# mainBoard.net
KiCad netlist of a schematic drawn in EAGLE
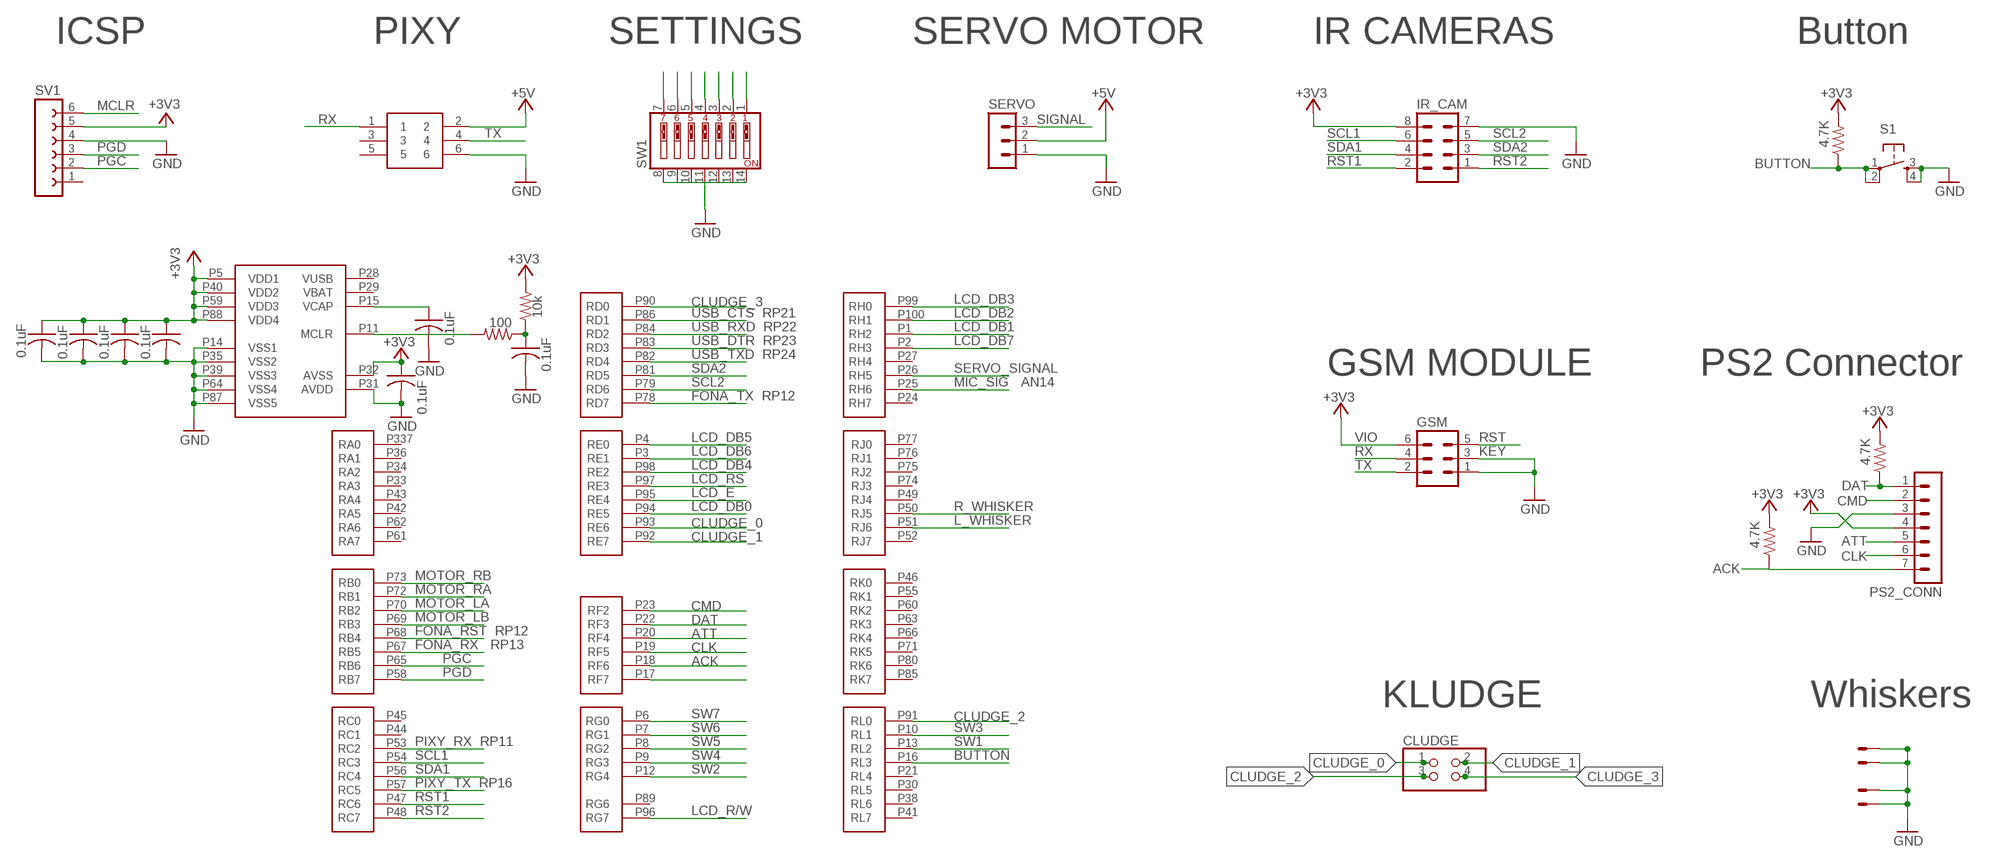
[diagram p0: schematic, sheet 1]
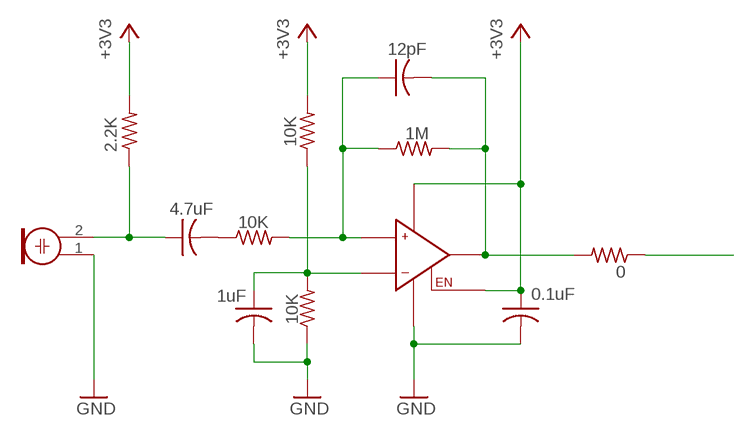
[diagram p1: schematic, sheet 2]
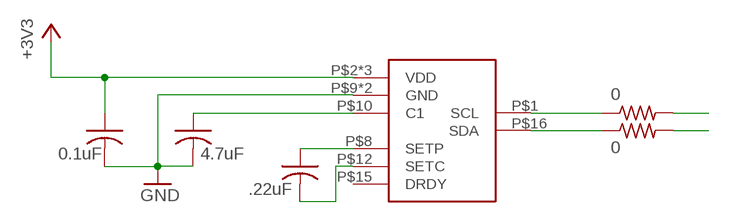
[diagram p2: schematic, sheet 3]
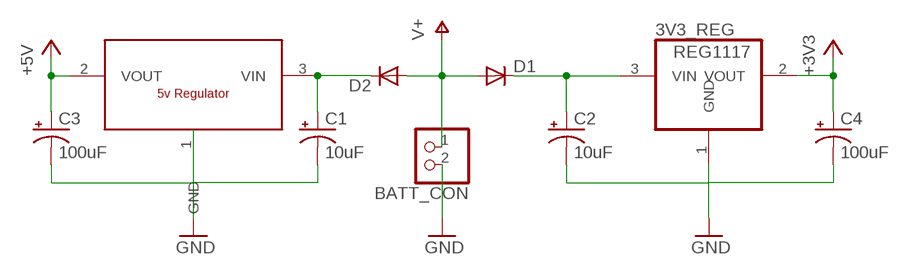
[diagram p3: schematic, sheet 4]
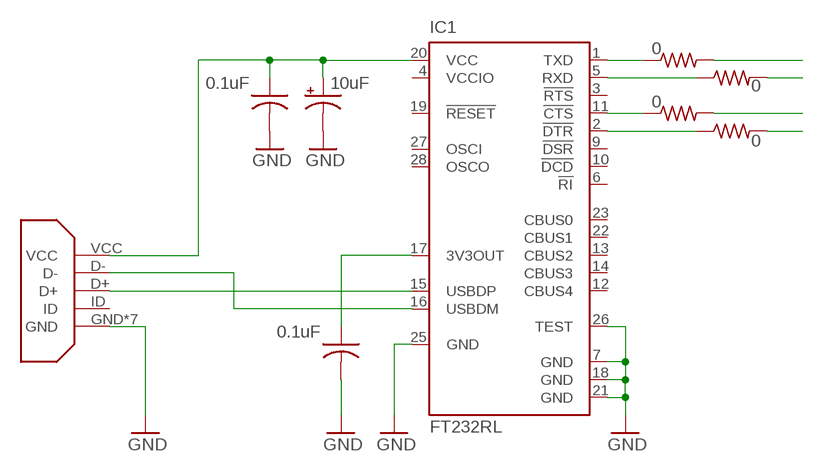
[diagram p4: schematic, sheet 5]
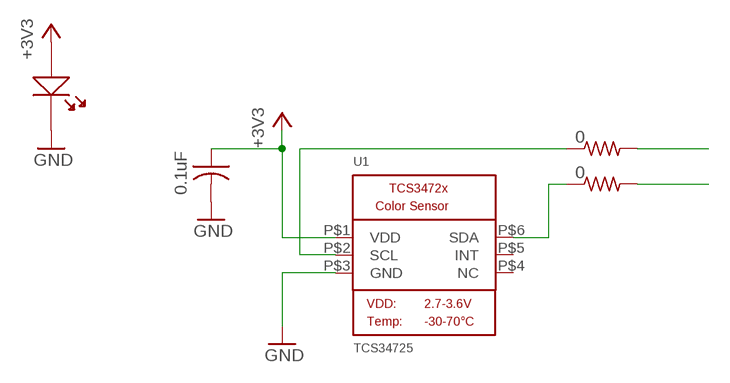
[diagram p5: schematic, sheet 6]
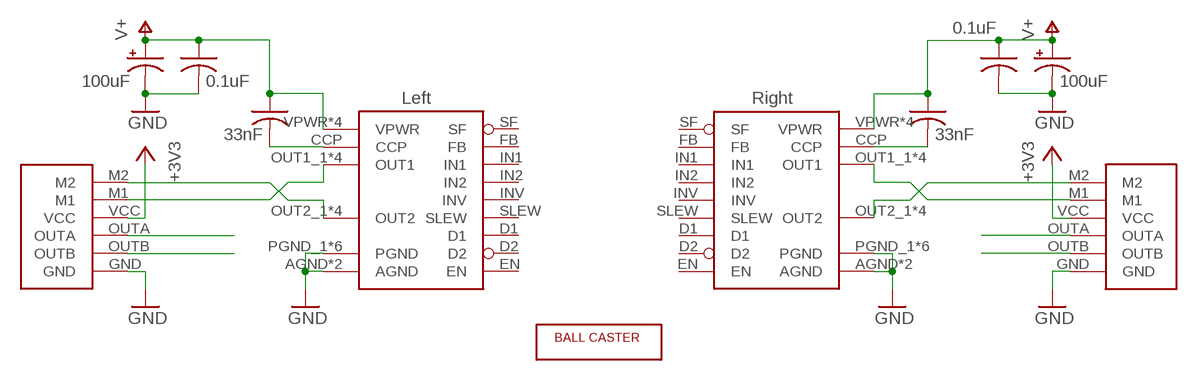
[diagram p6: schematic, sheet 7]
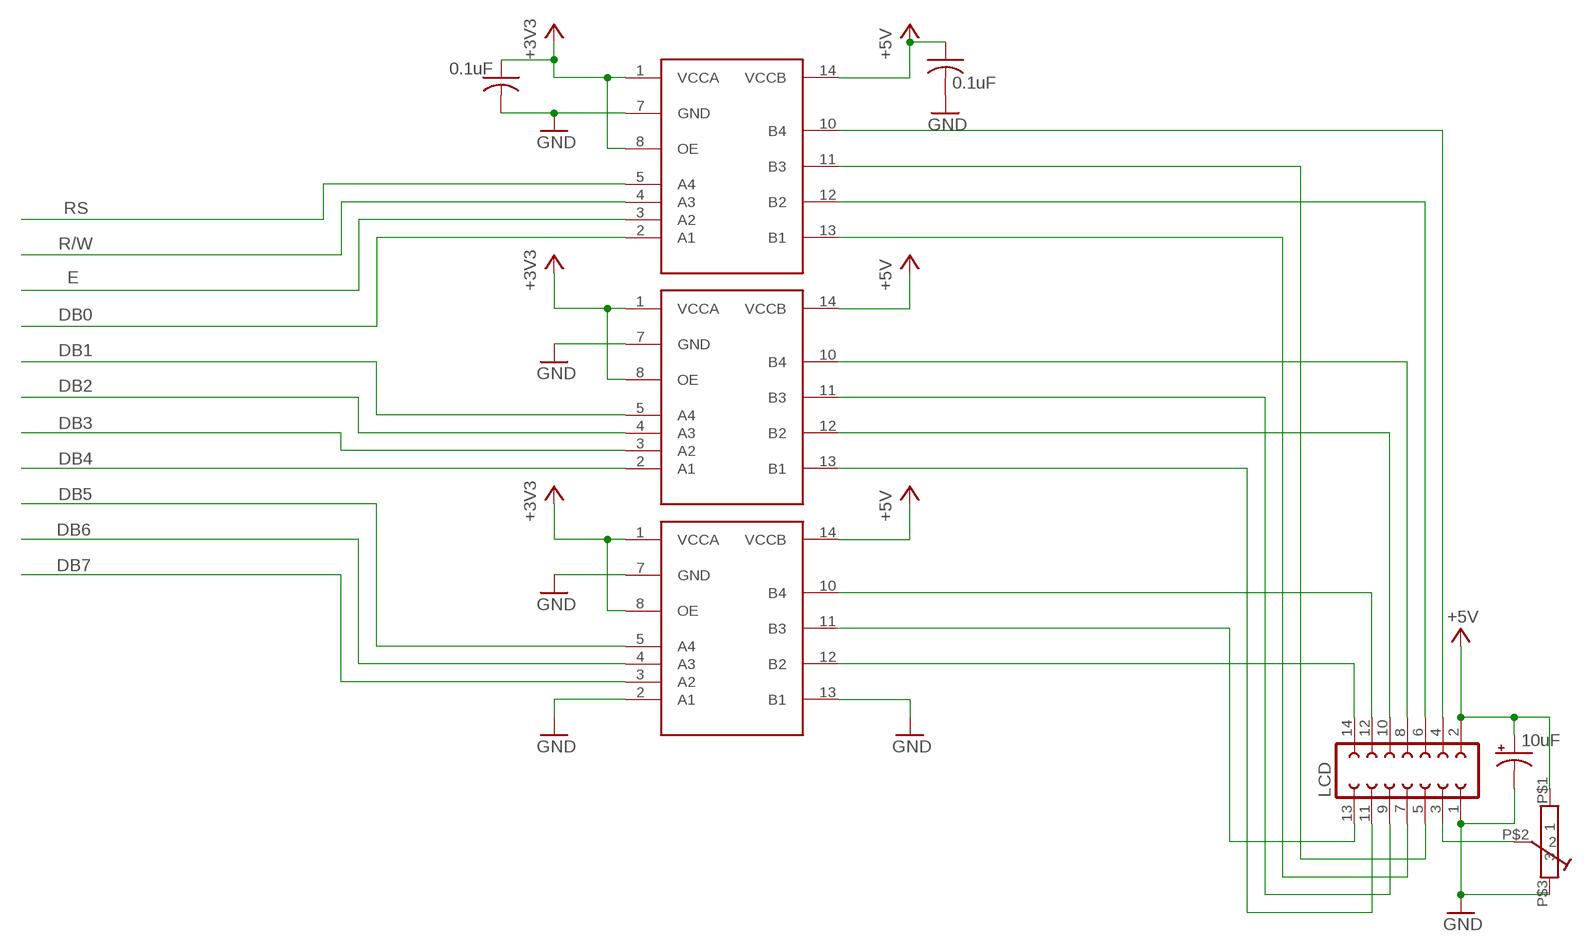
[diagram p7: schematic, sheet 8]

(export (version "E")
  (design (tool "Eeschema 10.0.6"))
  (components
    (comp (ref "C15")
      (value "0.1uF")
      (footprint "eagle-import:C0805")
      (libsource (lib "eagle-import") (part "C-USC0805"))
    )
    (comp (ref "R14")
      (value "0")
      (footprint "eagle-import:R0805")
      (libsource (lib "eagle-import") (part "R-US_R0805"))
    )
    (comp (ref "R15")
      (value "0")
      (footprint "eagle-import:R0805")
      (libsource (lib "eagle-import") (part "R-US_R0805"))
    )
    (comp (ref "U$5")
      (value "LED")
      (footprint "eagle-import:LED")
      (libsource (lib "eagle-import") (part "LED"))
    )
    (comp (ref "U1")
      (value "TCS34725")
      (footprint "eagle-import:TCS3472_FN6")
      (libsource (lib "eagle-import") (part "LIGHT_TCS3472"))
    )
    (comp (ref "C22")
      (value "33nF")
      (footprint "eagle-import:C0805")
      (libsource (lib "eagle-import") (part "C-USC0805"))
    )
    (comp (ref "C23")
      (value "0.1uF")
      (footprint "eagle-import:C0805")
      (libsource (lib "eagle-import") (part "C-USC0805"))
    )
    (comp (ref "C24")
      (value "100uF")
      (footprint "eagle-import:UD-4X5,8_NICHICON")
      (libsource (lib "eagle-import") (part "CPOL-USUD-4X5,8"))
    )
    (comp (ref "C25")
      (value "33nF")
      (footprint "eagle-import:C0805")
      (libsource (lib "eagle-import") (part "C-USC0805"))
    )
    (comp (ref "C26")
      (value "0.1uF")
      (footprint "eagle-import:C0805")
      (libsource (lib "eagle-import") (part "C-USC0805"))
    )
    (comp (ref "C27")
      (value "100uF")
      (footprint "eagle-import:UD-4X5,8_NICHICON")
      (libsource (lib "eagle-import") (part "CPOL-USUD-4X5,8"))
    )
    (comp (ref "U$7")
      (value "POLOLU_BALLCASTER")
      (footprint "eagle-import:CASTER")
      (libsource (lib "eagle-import") (part "POLOLU_BALLCASTER"))
    )
    (comp (ref "U$8")
      (value "POLOLU_MOTORDRIVE")
      (footprint "eagle-import:MOTOR")
      (libsource (lib "eagle-import") (part "POLOLU_MOTORDRIVE"))
    )
    (comp (ref "U$9")
      (value "POLOLU_MOTORDRIVE")
      (footprint "eagle-import:MOTOR")
      (libsource (lib "eagle-import") (part "POLOLU_MOTORDRIVE"))
    )
    (comp (ref "U$10")
      (value "MOTORDRIVE")
      (footprint "eagle-import:PQFN")
      (libsource (lib "eagle-import") (part "MOTORDRIVE"))
    )
    (comp (ref "U$11")
      (value "MOTORDRIVE")
      (footprint "eagle-import:PQFN")
      (libsource (lib "eagle-import") (part "MOTORDRIVE"))
    )
    (comp (ref "C16")
      (value "0.1uF")
      (footprint "eagle-import:C0805")
      (libsource (lib "eagle-import") (part "C-USC0805"))
    )
    (comp (ref "C18")
      (value "0.1uF")
      (footprint "eagle-import:C0805")
      (libsource (lib "eagle-import") (part "C-USC0805"))
    )
    (comp (ref "C19")
      (value "0.1uF")
      (footprint "eagle-import:C0805")
      (libsource (lib "eagle-import") (part "C-USC0805"))
    )
    (comp (ref "C20")
      (value "0.1uF")
      (footprint "eagle-import:C0805")
      (libsource (lib "eagle-import") (part "C-USC0805"))
    )
    (comp (ref "C28")
      (value "0.1uF")
      (footprint "eagle-import:C0805")
      (libsource (lib "eagle-import") (part "C-USC0805"))
    )
    (comp (ref "C29")
      (value "0.1uF")
      (footprint "eagle-import:C0805")
      (libsource (lib "eagle-import") (part "C-USC0805"))
    )
    (comp (ref "C30")
      (value "0.1uF")
      (footprint "eagle-import:C0805")
      (libsource (lib "eagle-import") (part "C-USC0805"))
    )
    (comp (ref "CLUDGE")
      (value "PINHD-2X2")
      (footprint "eagle-import:2X02")
      (libsource (lib "eagle-import") (part "PINHD-2X2"))
    )
    (comp (ref "GSM")
      (value "MA03-2")
      (footprint "eagle-import:MA03-2")
      (libsource (lib "eagle-import") (part "MA03-2"))
    )
    (comp (ref "IR_CAM")
      (value "MA04-2")
      (footprint "eagle-import:MA04-2")
      (libsource (lib "eagle-import") (part "MA04-2"))
    )
    (comp (ref "PS2_CONN")
      (value "MA07-1")
      (footprint "eagle-import:MA07-1")
      (libsource (lib "eagle-import") (part "MA07-1"))
    )
    (comp (ref "R16")
      (value "100")
      (footprint "eagle-import:R0805")
      (libsource (lib "eagle-import") (part "R-US_R0805"))
    )
    (comp (ref "R17")
      (value "10k")
      (footprint "eagle-import:R0805")
      (libsource (lib "eagle-import") (part "R-US_R0805"))
    )
    (comp (ref "R18")
      (value "4.7K")
      (footprint "eagle-import:M0805")
      (libsource (lib "eagle-import") (part "resistor_R-US_M0805"))
    )
    (comp (ref "R19")
      (value "4.7K")
      (footprint "eagle-import:M0805")
      (libsource (lib "eagle-import") (part "resistor_R-US_M0805"))
    )
    (comp (ref "R20")
      (value "4.7K")
      (footprint "eagle-import:M0805")
      (libsource (lib "eagle-import") (part "resistor_R-US_M0805"))
    )
    (comp (ref "S1")
      (value "10-XX")
      (footprint "eagle-import:B3F-10XX")
      (fields (field (name "MPN") "B3F-1000"))
      (libsource (lib "eagle-import") (part "10-XX"))
    )
    (comp (ref "SERVO")
      (value "MA03-1")
      (footprint "eagle-import:MA03-1")
      (libsource (lib "eagle-import") (part "MA03-1"))
    )
    (comp (ref "SV1")
      (value "FE06-1")
      (footprint "eagle-import:FE06")
      (libsource (lib "eagle-import") (part "FE06-1"))
    )
    (comp (ref "SW1")
      (value "SW_DIP-7")
      (footprint "eagle-import:EDG-07")
      (libsource (lib "eagle-import") (part "SW_DIP-7"))
    )
    (comp (ref "U$1")
      (value "PIC18F97J94")
      (footprint "eagle-import:QTFP-100")
      (libsource (lib "eagle-import") (part "PIC18F97J94"))
    )
    (comp (ref "U$15")
      (value "PIXY")
      (footprint "eagle-import:PIXY_HEADER")
      (libsource (lib "eagle-import") (part "PIXY"))
    )
    (comp (ref "X1")
      (value "22-23-2021")
      (footprint "eagle-import:22-23-2021")
      (fields (field (name "MF") "MOLEX"))
      (libsource (lib "eagle-import") (part "22-23-2021"))
    )
    (comp (ref "X2")
      (value "22-23-2021")
      (footprint "eagle-import:22-23-2021")
      (fields (field (name "MF") "MOLEX"))
      (libsource (lib "eagle-import") (part "22-23-2021"))
    )
    (comp (ref "10UF")
      (value "10uF")
      (footprint "eagle-import:UD-4X5,8_NICHICON")
      (libsource (lib "eagle-import") (part "CPOL-USUD-4X5,8"))
    )
    (comp (ref "C17")
      (value "0.1uF")
      (footprint "eagle-import:C0805")
      (libsource (lib "eagle-import") (part "C-USC0805"))
    )
    (comp (ref "C21")
      (value "0.1uF")
      (footprint "eagle-import:C0805")
      (libsource (lib "eagle-import") (part "C-USC0805"))
    )
    (comp (ref "LCD")
      (value "FE07-2")
      (footprint "eagle-import:FE07-2")
      (libsource (lib "eagle-import") (part "FE07-2"))
    )
    (comp (ref "U$6")
      (value "PVG3G-SMD-TRIMMER")
      (footprint "eagle-import:PVG3G-SMT-TRIMMER")
      (libsource (lib "eagle-import") (part "PVG3G-SMD-TRIMMER"))
    )
    (comp (ref "U$12")
      (value "TXB0104")
      (footprint "eagle-import:S-PVQFN-N14")
      (libsource (lib "eagle-import") (part "TXB0104"))
    )
    (comp (ref "U$13")
      (value "TXB0104")
      (footprint "eagle-import:S-PVQFN-N14")
      (libsource (lib "eagle-import") (part "TXB0104"))
    )
    (comp (ref "U$14")
      (value "TXB0104")
      (footprint "eagle-import:S-PVQFN-N14")
      (libsource (lib "eagle-import") (part "TXB0104"))
    )
    (comp (ref "C11")
      (value "1uF")
      (footprint "eagle-import:C0805")
      (libsource (lib "eagle-import") (part "C-USC0805"))
    )
    (comp (ref "C12")
      (value "4.7uF")
      (footprint "eagle-import:C0805")
      (libsource (lib "eagle-import") (part "C-USC0805"))
    )
    (comp (ref "C13")
      (value "12pF")
      (footprint "eagle-import:C0805")
      (libsource (lib "eagle-import") (part "C-USC0805"))
    )
    (comp (ref "C14")
      (value "0.1uF")
      (footprint "eagle-import:C0805")
      (libsource (lib "eagle-import") (part "C-USC0805"))
    )
    (comp (ref "M1")
      (value "ELECTRET_MICROPHON-WM-63PR")
      (footprint "eagle-import:WM-63PR")
      (libsource (lib "eagle-import") (part "ELECTRET_MICROPHON-WM-63PR"))
    )
    (comp (ref "R1")
      (value "10K")
      (footprint "eagle-import:R0805")
      (libsource (lib "eagle-import") (part "R-US_R0805"))
    )
    (comp (ref "R2")
      (value "1M")
      (footprint "eagle-import:R0805")
      (libsource (lib "eagle-import") (part "R-US_R0805"))
    )
    (comp (ref "R4")
      (value "2.2K")
      (footprint "eagle-import:R0805")
      (libsource (lib "eagle-import") (part "R-US_R0805"))
    )
    (comp (ref "R5")
      (value "10K")
      (footprint "eagle-import:R0805")
      (libsource (lib "eagle-import") (part "R-US_R0805"))
    )
    (comp (ref "R6")
      (value "10K")
      (footprint "eagle-import:R0805")
      (libsource (lib "eagle-import") (part "R-US_R0805"))
    )
    (comp (ref "R7")
      (value "0")
      (footprint "eagle-import:R0805")
      (libsource (lib "eagle-import") (part "R-US_R0805"))
    )
    (comp (ref "U$4")
      (value "OPA334")
      (footprint "eagle-import:OPA334")
      (libsource (lib "eagle-import") (part "OPA334"))
    )
    (comp (ref "3V3_REG")
      (value "REG1117")
      (footprint "eagle-import:SOT223")
      (libsource (lib "eagle-import") (part "REG1117"))
    )
    (comp (ref "5V_REG")
      (value "NCP1117-DPAK")
      (footprint "eagle-import:DPAK-2")
      (libsource (lib "eagle-import") (part "NCP1117-DPAK"))
    )
    (comp (ref "BATT_CON")
      (value "JST_2PIN-THM")
      (footprint "eagle-import:JST-PH-2-THM")
      (libsource (lib "eagle-import") (part "JST_2PIN-THM"))
    )
    (comp (ref "C1")
      (value "10uF")
      (footprint "eagle-import:UD-4X5,8_NICHICON")
      (libsource (lib "eagle-import") (part "CPOL-USUD-4X5,8"))
    )
    (comp (ref "C2")
      (value "10uF")
      (footprint "eagle-import:UD-4X5,8_NICHICON")
      (libsource (lib "eagle-import") (part "CPOL-USUD-4X5,8"))
    )
    (comp (ref "C3")
      (value "100uF")
      (footprint "eagle-import:UD-6,3X5,8_NICHICON")
      (libsource (lib "eagle-import") (part "CPOL-USUD-6,3X5,8"))
    )
    (comp (ref "C4")
      (value "100uF")
      (footprint "eagle-import:UD-6,3X5,8_NICHICON")
      (libsource (lib "eagle-import") (part "CPOL-USUD-6,3X5,8"))
    )
    (comp (ref "D1")
      (value "DIODE-SOD123")
      (footprint "eagle-import:SOD123")
      (libsource (lib "eagle-import") (part "DIODE-SOD123"))
    )
    (comp (ref "D2")
      (value "DIODE-SOD123")
      (footprint "eagle-import:SOD123")
      (libsource (lib "eagle-import") (part "DIODE-SOD123"))
    )
    (comp (ref "C8")
      (value ".22uF")
      (footprint "eagle-import:C0805")
      (libsource (lib "eagle-import") (part "C-USC0805"))
    )
    (comp (ref "C9")
      (value "4.7uF")
      (footprint "eagle-import:C0805")
      (libsource (lib "eagle-import") (part "C-USC0805"))
    )
    (comp (ref "C10")
      (value "0.1uF")
      (footprint "eagle-import:C0805")
      (libsource (lib "eagle-import") (part "C-USC0805"))
    )
    (comp (ref "R8")
      (value "0")
      (footprint "eagle-import:R0805")
      (libsource (lib "eagle-import") (part "R-US_R0805"))
    )
    (comp (ref "R9")
      (value "0")
      (footprint "eagle-import:R0805")
      (libsource (lib "eagle-import") (part "R-US_R0805"))
    )
    (comp (ref "U$3")
      (value "HMC5883L")
      (footprint "eagle-import:HMC5883L")
      (libsource (lib "eagle-import") (part "HMC5883L"))
    )
    (comp (ref "C5")
      (value "0.1uF")
      (footprint "eagle-import:C0805")
      (libsource (lib "eagle-import") (part "C-USC0805"))
    )
    (comp (ref "C6")
      (value "10uF")
      (footprint "eagle-import:UD-4X5,8_NICHICON")
      (libsource (lib "eagle-import") (part "CPOL-USUD-4X5,8"))
    )
    (comp (ref "C7")
      (value "0.1uF")
      (footprint "eagle-import:C0805")
      (libsource (lib "eagle-import") (part "C-USC0805"))
    )
    (comp (ref "IC1")
      (value "FT232RL")
      (footprint "eagle-import:SSOP28")
      (libsource (lib "eagle-import") (part "FT232RL"))
    )
    (comp (ref "R10")
      (value "0")
      (footprint "eagle-import:R0805")
      (libsource (lib "eagle-import") (part "R-US_R0805"))
    )
    (comp (ref "R11")
      (value "0")
      (footprint "eagle-import:R0805")
      (libsource (lib "eagle-import") (part "R-US_R0805"))
    )
    (comp (ref "R12")
      (value "0")
      (footprint "eagle-import:R0805")
      (libsource (lib "eagle-import") (part "R-US_R0805"))
    )
    (comp (ref "R13")
      (value "0")
      (footprint "eagle-import:R0805")
      (libsource (lib "eagle-import") (part "R-US_R0805"))
    )
    (comp (ref "U$2")
      (value "MICRO_USB")
      (footprint "eagle-import:MICRO_USB_FCI")
      (libsource (lib "eagle-import") (part "MICRO_USB"))
    )
  )
  (nets
    (net (code "1") (name "+3V3") (class "Default")
      (node (ref "3V3_REG") (pin "2") (pinfunction "VOUT_2") (pintype "output"))
      (node (ref "C10") (pin "1") (pinfunction "1_1") (pintype "passive"))
      (node (ref "C14") (pin "1") (pinfunction "1_1") (pintype "passive"))
      (node (ref "C15") (pin "1") (pinfunction "1_1") (pintype "passive"))
      (node (ref "C16") (pin "1") (pinfunction "1_1") (pintype "passive"))
      (node (ref "C17") (pin "1") (pinfunction "1_1") (pintype "passive"))
      (node (ref "C18") (pin "1") (pinfunction "1_1") (pintype "passive"))
      (node (ref "C19") (pin "1") (pinfunction "1_1") (pintype "passive"))
      (node (ref "C20") (pin "1") (pinfunction "1_1") (pintype "passive"))
      (node (ref "C28") (pin "1") (pinfunction "1_1") (pintype "passive"))
      (node (ref "C4") (pin "+") (pinfunction "+_+") (pintype "passive"))
      (node (ref "GSM") (pin "6") (pinfunction "6_6") (pintype "passive"))
      (node (ref "IR_CAM") (pin "8") (pinfunction "8_8") (pintype "passive"))
      (node (ref "PS2_CONN") (pin "4") (pinfunction "4_4") (pintype "passive"))
      (node (ref "R17") (pin "2") (pinfunction "2_2") (pintype "passive"))
      (node (ref "R18") (pin "2") (pinfunction "2_2") (pintype "passive"))
      (node (ref "R19") (pin "2") (pinfunction "2_2") (pintype "passive"))
      (node (ref "R20") (pin "2") (pinfunction "2_2") (pintype "passive"))
      (node (ref "R4") (pin "2") (pinfunction "2_2") (pintype "passive"))
      (node (ref "R5") (pin "2") (pinfunction "2_2") (pintype "passive"))
      (node (ref "SV1") (pin "5") (pinfunction "5_5") (pintype "passive"))
      (node (ref "U$1") (pin "P32") (pinfunction "AVSS_P32") (pintype "bidirectional"))
      (node (ref "U$1") (pin "P40") (pinfunction "VDD2_P40") (pintype "bidirectional"))
      (node (ref "U$1") (pin "P5") (pinfunction "VDD1_P5") (pintype "bidirectional"))
      (node (ref "U$1") (pin "P59") (pinfunction "VDD3_P59") (pintype "bidirectional"))
      (node (ref "U$1") (pin "P88") (pinfunction "VDD4_P88") (pintype "bidirectional"))
      (node (ref "U$12") (pin "1") (pinfunction "VCCA_1") (pintype "power_in"))
      (node (ref "U$12") (pin "8") (pinfunction "OE_8") (pintype "bidirectional"))
      (node (ref "U$13") (pin "1") (pinfunction "VCCA_1") (pintype "power_in"))
      (node (ref "U$13") (pin "8") (pinfunction "OE_8") (pintype "bidirectional"))
      (node (ref "U$14") (pin "1") (pinfunction "VCCA_1") (pintype "power_in"))
      (node (ref "U$14") (pin "8") (pinfunction "OE_8") (pintype "bidirectional"))
      (node (ref "U$3") (pin "P$13") (pinfunction "VDD_P$13") (pintype "bidirectional"))
      (node (ref "U$3") (pin "P$2") (pinfunction "VDD_P$2") (pintype "bidirectional"))
      (node (ref "U$3") (pin "P$4") (pinfunction "VDD_P$4") (pintype "bidirectional"))
      (node (ref "U$4") (pin "P$5") (pinfunction "EN_P$5") (pintype "bidirectional"))
      (node (ref "U$4") (pin "P$6") (pinfunction "V+_P$6") (pintype "bidirectional"))
      (node (ref "U$5") (pin "ANODE") (pinfunction "ANODE_ANODE") (pintype "bidirectional"))
      (node (ref "U$8") (pin "VCC") (pinfunction "VCC_VCC") (pintype "bidirectional"))
      (node (ref "U$9") (pin "VCC") (pinfunction "VCC_VCC") (pintype "bidirectional"))
      (node (ref "U1") (pin "P$1") (pinfunction "VDD_P$1") (pintype "power_in"))
    )
    (net (code "2") (name "+5V") (class "Default")
      (node (ref "10UF") (pin "+") (pinfunction "+_+") (pintype "passive"))
      (node (ref "5V_REG") (pin "2") (pinfunction "VOUT_2") (pintype "bidirectional"))
      (node (ref "C21") (pin "1") (pinfunction "1_1") (pintype "passive"))
      (node (ref "C3") (pin "+") (pinfunction "+_+") (pintype "passive"))
      (node (ref "LCD") (pin "2") (pinfunction "2_2") (pintype "passive"))
      (node (ref "SERVO") (pin "2") (pinfunction "2_2") (pintype "passive"))
      (node (ref "U$12") (pin "14") (pinfunction "VCCB_14") (pintype "power_in"))
      (node (ref "U$13") (pin "14") (pinfunction "VCCB_14") (pintype "power_in"))
      (node (ref "U$14") (pin "14") (pinfunction "VCCB_14") (pintype "power_in"))
      (node (ref "U$15") (pin "2") (pinfunction "2_2") (pintype "bidirectional"))
      (node (ref "U$6") (pin "P$1") (pinfunction "1_P$1") (pintype "power_in"))
    )
    (net (code "3") (name "ACK") (class "Default")
      (node (ref "PS2_CONN") (pin "7") (pinfunction "7_7") (pintype "passive"))
      (node (ref "R20") (pin "1") (pinfunction "1_1") (pintype "passive"))
      (node (ref "U$1") (pin "P18") (pinfunction "RF6_P18") (pintype "bidirectional"))
    )
    (net (code "4") (name "ATT") (class "Default")
      (node (ref "PS2_CONN") (pin "5") (pinfunction "5_5") (pintype "passive"))
      (node (ref "U$1") (pin "P20") (pinfunction "RF4_P20") (pintype "bidirectional"))
    )
    (net (code "5") (name "BUTTON") (class "Default")
      (node (ref "R18") (pin "1") (pinfunction "1_1") (pintype "passive"))
      (node (ref "S1") (pin "1") (pinfunction "P_1") (pintype "passive"))
      (node (ref "S1") (pin "2") (pinfunction "P1_2") (pintype "passive"))
      (node (ref "U$1") (pin "P16") (pinfunction "RL3_P16") (pintype "bidirectional"))
    )
    (net (code "6") (name "CLK") (class "Default")
      (node (ref "PS2_CONN") (pin "6") (pinfunction "6_6") (pintype "passive"))
      (node (ref "U$1") (pin "P19") (pinfunction "RF5_P19") (pintype "bidirectional"))
    )
    (net (code "7") (name "CLUDGE_0") (class "Default")
      (node (ref "CLUDGE") (pin "1") (pinfunction "1_1") (pintype "passive"))
      (node (ref "U$1") (pin "P93") (pinfunction "RE6_P93") (pintype "bidirectional"))
    )
    (net (code "8") (name "CLUDGE_1") (class "Default")
      (node (ref "CLUDGE") (pin "2") (pinfunction "2_2") (pintype "passive"))
      (node (ref "U$1") (pin "P92") (pinfunction "RE7_P92") (pintype "bidirectional"))
    )
    (net (code "9") (name "CLUDGE_2") (class "Default")
      (node (ref "CLUDGE") (pin "3") (pinfunction "3_3") (pintype "passive"))
      (node (ref "U$1") (pin "P91") (pinfunction "RL0_P91") (pintype "bidirectional"))
    )
    (net (code "10") (name "CLUDGE_3") (class "Default")
      (node (ref "CLUDGE") (pin "4") (pinfunction "4_4") (pintype "passive"))
      (node (ref "U$1") (pin "P90") (pinfunction "RD0_P90") (pintype "bidirectional"))
    )
    (net (code "11") (name "CMD") (class "Default")
      (node (ref "PS2_CONN") (pin "2") (pinfunction "2_2") (pintype "passive"))
      (node (ref "U$1") (pin "P23") (pinfunction "RF2_P23") (pintype "bidirectional"))
    )
    (net (code "12") (name "DAT") (class "Default")
      (node (ref "PS2_CONN") (pin "1") (pinfunction "1_1") (pintype "passive"))
      (node (ref "R19") (pin "1") (pinfunction "1_1") (pintype "passive"))
      (node (ref "U$1") (pin "P22") (pinfunction "RF3_P22") (pintype "bidirectional"))
    )
    (net (code "13") (name "GND") (class "Default")
      (node (ref "10UF") (pin "-") (pinfunction "-_-") (pintype "passive"))
      (node (ref "3V3_REG") (pin "1") (pinfunction "GND_1") (pintype "power_in"))
      (node (ref "5V_REG") (pin "1") (pinfunction "GND_1") (pintype "bidirectional"))
      (node (ref "BATT_CON") (pin "2") (pinfunction "1_2") (pintype "passive"))
      (node (ref "C1") (pin "-") (pinfunction "-_-") (pintype "passive"))
      (node (ref "C10") (pin "2") (pinfunction "2_2") (pintype "passive"))
      (node (ref "C11") (pin "2") (pinfunction "2_2") (pintype "passive"))
      (node (ref "C14") (pin "2") (pinfunction "2_2") (pintype "passive"))
      (node (ref "C15") (pin "2") (pinfunction "2_2") (pintype "passive"))
      (node (ref "C16") (pin "2") (pinfunction "2_2") (pintype "passive"))
      (node (ref "C17") (pin "2") (pinfunction "2_2") (pintype "passive"))
      (node (ref "C18") (pin "2") (pinfunction "2_2") (pintype "passive"))
      (node (ref "C19") (pin "2") (pinfunction "2_2") (pintype "passive"))
      (node (ref "C2") (pin "-") (pinfunction "-_-") (pintype "passive"))
      (node (ref "C20") (pin "2") (pinfunction "2_2") (pintype "passive"))
      (node (ref "C21") (pin "2") (pinfunction "2_2") (pintype "passive"))
      (node (ref "C23") (pin "2") (pinfunction "2_2") (pintype "passive"))
      (node (ref "C24") (pin "-") (pinfunction "-_-") (pintype "passive"))
      (node (ref "C26") (pin "2") (pinfunction "2_2") (pintype "passive"))
      (node (ref "C27") (pin "-") (pinfunction "-_-") (pintype "passive"))
      (node (ref "C28") (pin "2") (pinfunction "2_2") (pintype "passive"))
      (node (ref "C29") (pin "2") (pinfunction "2_2") (pintype "passive"))
      (node (ref "C3") (pin "-") (pinfunction "-_-") (pintype "passive"))
      (node (ref "C30") (pin "2") (pinfunction "2_2") (pintype "passive"))
      (node (ref "C4") (pin "-") (pinfunction "-_-") (pintype "passive"))
      (node (ref "C5") (pin "2") (pinfunction "2_2") (pintype "passive"))
      (node (ref "C6") (pin "-") (pinfunction "-_-") (pintype "passive"))
      (node (ref "C7") (pin "2") (pinfunction "2_2") (pintype "passive"))
      (node (ref "C9") (pin "2") (pinfunction "2_2") (pintype "passive"))
      (node (ref "GSM") (pin "1") (pinfunction "1_1") (pintype "passive"))
      (node (ref "GSM") (pin "3") (pinfunction "3_3") (pintype "passive"))
      (node (ref "IC1") (pin "18") (pinfunction "GND_18") (pintype "power_in"))
      (node (ref "IC1") (pin "21") (pinfunction "GND_21") (pintype "power_in"))
      (node (ref "IC1") (pin "25") (pinfunction "GND_25") (pintype "power_in"))
      (node (ref "IC1") (pin "26") (pinfunction "TEST_26") (pintype "input"))
      (node (ref "IC1") (pin "7") (pinfunction "GND_7") (pintype "power_in"))
      (node (ref "IR_CAM") (pin "7") (pinfunction "7_7") (pintype "passive"))
      (node (ref "LCD") (pin "1") (pinfunction "1_1") (pintype "passive"))
      (node (ref "M1") (pin "1") (pinfunction "1_1") (pintype "passive"))
      (node (ref "PS2_CONN") (pin "3") (pinfunction "3_3") (pintype "passive"))
      (node (ref "R6") (pin "1") (pinfunction "1_1") (pintype "passive"))
      (node (ref "S1") (pin "3") (pinfunction "S_3") (pintype "passive"))
      (node (ref "S1") (pin "4") (pinfunction "S1_4") (pintype "passive"))
      (node (ref "SERVO") (pin "1") (pinfunction "1_1") (pintype "passive"))
      (node (ref "SV1") (pin "4") (pinfunction "4_4") (pintype "passive"))
      (node (ref "SW1") (pin "10") (pinfunction "10_10") (pintype "passive"))
      (node (ref "SW1") (pin "11") (pinfunction "11_11") (pintype "passive"))
      (node (ref "SW1") (pin "12") (pinfunction "12_12") (pintype "passive"))
      (node (ref "SW1") (pin "13") (pinfunction "13_13") (pintype "passive"))
      (node (ref "SW1") (pin "14") (pinfunction "14_14") (pintype "passive"))
      (node (ref "SW1") (pin "8") (pinfunction "8_8") (pintype "passive"))
      (node (ref "SW1") (pin "9") (pinfunction "9_9") (pintype "passive"))
      (node (ref "U$1") (pin "P14") (pinfunction "VSS1_P14") (pintype "bidirectional"))
      (node (ref "U$1") (pin "P31") (pinfunction "AVDD_P31") (pintype "bidirectional"))
      (node (ref "U$1") (pin "P35") (pinfunction "VSS2_P35") (pintype "bidirectional"))
      (node (ref "U$1") (pin "P39") (pinfunction "VSS3_P39") (pintype "bidirectional"))
      (node (ref "U$1") (pin "P64") (pinfunction "VSS4_P64") (pintype "bidirectional"))
      (node (ref "U$1") (pin "P87") (pinfunction "VSS5_P87") (pintype "bidirectional"))
      (node (ref "U$10") (pin "AGND") (pinfunction "AGND_AGND") (pintype "bidirectional"))
      (node (ref "U$10") (pin "AGND_L") (pinfunction "AGND_AGND_L") (pintype "bidirectional"))
      (node (ref "U$10") (pin "PGND_1") (pinfunction "PGND_PGND_1") (pintype "bidirectional"))
      (node (ref "U$10") (pin "PGND_2") (pinfunction "PGND_PGND_2") (pintype "bidirectional"))
      (node (ref "U$10") (pin "PGND_3") (pinfunction "PGND_PGND_3") (pintype "bidirectional"))
      (node (ref "U$10") (pin "PGND_4") (pinfunction "PGND_PGND_4") (pintype "bidirectional"))
      (node (ref "U$10") (pin "PGND_5") (pinfunction "PGND_PGND_5") (pintype "bidirectional"))
      (node (ref "U$10") (pin "PGND_6") (pinfunction "PGND_PGND_6") (pintype "bidirectional"))
      (node (ref "U$11") (pin "AGND") (pinfunction "AGND_AGND") (pintype "bidirectional"))
      (node (ref "U$11") (pin "AGND_L") (pinfunction "AGND_AGND_L") (pintype "bidirectional"))
      (node (ref "U$11") (pin "PGND_1") (pinfunction "PGND_PGND_1") (pintype "bidirectional"))
      (node (ref "U$11") (pin "PGND_2") (pinfunction "PGND_PGND_2") (pintype "bidirectional"))
      (node (ref "U$11") (pin "PGND_3") (pinfunction "PGND_PGND_3") (pintype "bidirectional"))
      (node (ref "U$11") (pin "PGND_4") (pinfunction "PGND_PGND_4") (pintype "bidirectional"))
      (node (ref "U$11") (pin "PGND_5") (pinfunction "PGND_PGND_5") (pintype "bidirectional"))
      (node (ref "U$11") (pin "PGND_6") (pinfunction "PGND_PGND_6") (pintype "bidirectional"))
      (node (ref "U$12") (pin "7") (pinfunction "GND_7") (pintype "power_in"))
      (node (ref "U$13") (pin "7") (pinfunction "GND_7") (pintype "power_in"))
      (node (ref "U$14") (pin "13") (pinfunction "B1_13") (pintype "bidirectional"))
      (node (ref "U$14") (pin "2") (pinfunction "A1_2") (pintype "bidirectional"))
      (node (ref "U$14") (pin "7") (pinfunction "GND_7") (pintype "power_in"))
      (node (ref "U$15") (pin "6") (pinfunction "6_6") (pintype "bidirectional"))
      (node (ref "U$2") (pin "GND") (pinfunction "GND_GND") (pintype "bidirectional"))
      (node (ref "U$2") (pin "GND1") (pinfunction "GND_GND1") (pintype "bidirectional"))
      (node (ref "U$2") (pin "GND2") (pinfunction "GND_GND2") (pintype "bidirectional"))
      (node (ref "U$2") (pin "P$1") (pinfunction "GND_P$1") (pintype "bidirectional"))
      (node (ref "U$2") (pin "P$2") (pinfunction "GND_P$2") (pintype "bidirectional"))
      (node (ref "U$2") (pin "P$3") (pinfunction "GND_P$3") (pintype "bidirectional"))
      (node (ref "U$2") (pin "P$4") (pinfunction "GND_P$4") (pintype "bidirectional"))
      (node (ref "U$3") (pin "P$11") (pinfunction "GND_P$11") (pintype "bidirectional"))
      (node (ref "U$3") (pin "P$9") (pinfunction "GND_P$9") (pintype "bidirectional"))
      (node (ref "U$4") (pin "P$2") (pinfunction "V-_P$2") (pintype "bidirectional"))
      (node (ref "U$5") (pin "CATHODE") (pinfunction "CATHODE_CATHODE") (pintype "bidirectional"))
      (node (ref "U$6") (pin "P$3") (pinfunction "3_P$3") (pintype "power_in"))
      (node (ref "U$8") (pin "GND") (pinfunction "GND_GND") (pintype "bidirectional"))
      (node (ref "U$9") (pin "GND") (pinfunction "GND_GND") (pintype "bidirectional"))
      (node (ref "U1") (pin "P$3") (pinfunction "GND_P$3") (pintype "power_in"))
      (node (ref "X1") (pin "1") (pinfunction "S_1") (pintype "passive"))
      (node (ref "X1") (pin "2") (pinfunction "S_2") (pintype "passive"))
      (node (ref "X2") (pin "1") (pinfunction "S_1") (pintype "passive"))
      (node (ref "X2") (pin "2") (pinfunction "S_2") (pintype "passive"))
    )
    (net (code "14") (name "GSM_RST") (class "Default")
      (node (ref "GSM") (pin "5") (pinfunction "5_5") (pintype "passive"))
      (node (ref "U$1") (pin "P68") (pinfunction "RB4_P68") (pintype "bidirectional"))
    )
    (net (code "15") (name "GSM_RX") (class "Default")
      (node (ref "GSM") (pin "4") (pinfunction "4_4") (pintype "passive"))
      (node (ref "U$1") (pin "P67") (pinfunction "RB5_P67") (pintype "bidirectional"))
    )
    (net (code "16") (name "GSM_TX") (class "Default")
      (node (ref "GSM") (pin "2") (pinfunction "2_2") (pintype "passive"))
      (node (ref "U$1") (pin "P78") (pinfunction "RD7_P78") (pintype "bidirectional"))
    )
    (net (code "17") (name "I2C_SCL") (class "Default")
      (node (ref "IR_CAM") (pin "6") (pinfunction "6_6") (pintype "passive"))
      (node (ref "R15") (pin "2") (pinfunction "2_2") (pintype "passive"))
      (node (ref "R8") (pin "2") (pinfunction "2_2") (pintype "passive"))
      (node (ref "U$1") (pin "P79") (pinfunction "RD6_P79") (pintype "bidirectional"))
    )
    (net (code "18") (name "I2C_SCL1") (class "Default")
      (node (ref "IR_CAM") (pin "5") (pinfunction "5_5") (pintype "passive"))
      (node (ref "U$1") (pin "P54") (pinfunction "RC3_P54") (pintype "bidirectional"))
    )
    (net (code "19") (name "I2C_SDA") (class "Default")
      (node (ref "IR_CAM") (pin "4") (pinfunction "4_4") (pintype "passive"))
      (node (ref "R14") (pin "2") (pinfunction "2_2") (pintype "passive"))
      (node (ref "R9") (pin "2") (pinfunction "2_2") (pintype "passive"))
      (node (ref "U$1") (pin "P81") (pinfunction "RD5_P81") (pintype "bidirectional"))
    )
    (net (code "20") (name "I2C_SDA1") (class "Default")
      (node (ref "IR_CAM") (pin "3") (pinfunction "3_3") (pintype "passive"))
      (node (ref "U$1") (pin "P56") (pinfunction "RC4_P56") (pintype "bidirectional"))
    )
    (net (code "21") (name "LCD_DB0") (class "Default")
      (node (ref "U$1") (pin "P94") (pinfunction "RE5_P94") (pintype "bidirectional"))
      (node (ref "U$12") (pin "2") (pinfunction "A1_2") (pintype "bidirectional"))
    )
    (net (code "22") (name "LCD_DB1") (class "Default")
      (node (ref "U$1") (pin "P1") (pinfunction "RH2_P1") (pintype "bidirectional"))
      (node (ref "U$13") (pin "5") (pinfunction "A4_5") (pintype "bidirectional"))
    )
    (net (code "23") (name "LCD_DB2") (class "Default")
      (node (ref "U$1") (pin "P100") (pinfunction "RH1_P100") (pintype "bidirectional"))
      (node (ref "U$13") (pin "4") (pinfunction "A3_4") (pintype "bidirectional"))
    )
    (net (code "24") (name "LCD_DB3") (class "Default")
      (node (ref "U$1") (pin "P99") (pinfunction "RH0_P99") (pintype "bidirectional"))
      (node (ref "U$13") (pin "3") (pinfunction "A2_3") (pintype "bidirectional"))
    )
    (net (code "25") (name "LCD_DB4") (class "Default")
      (node (ref "U$1") (pin "P98") (pinfunction "RE2_P98") (pintype "bidirectional"))
      (node (ref "U$13") (pin "2") (pinfunction "A1_2") (pintype "bidirectional"))
    )
    (net (code "26") (name "LCD_DB5") (class "Default")
      (node (ref "U$1") (pin "P4") (pinfunction "RE0_P4") (pintype "bidirectional"))
      (node (ref "U$14") (pin "5") (pinfunction "A4_5") (pintype "bidirectional"))
    )
    (net (code "27") (name "LCD_DB6") (class "Default")
      (node (ref "U$1") (pin "P3") (pinfunction "RE1_P3") (pintype "bidirectional"))
      (node (ref "U$14") (pin "4") (pinfunction "A3_4") (pintype "bidirectional"))
    )
    (net (code "28") (name "LCD_DB7") (class "Default")
      (node (ref "U$1") (pin "P2") (pinfunction "RH3_P2") (pintype "bidirectional"))
      (node (ref "U$14") (pin "3") (pinfunction "A2_3") (pintype "bidirectional"))
    )
    (net (code "29") (name "LCD_E") (class "Default")
      (node (ref "U$1") (pin "P95") (pinfunction "RE4_P95") (pintype "bidirectional"))
      (node (ref "U$12") (pin "3") (pinfunction "A2_3") (pintype "bidirectional"))
    )
    (net (code "30") (name "LCD_RS") (class "Default")
      (node (ref "U$1") (pin "P97") (pinfunction "RE3_P97") (pintype "bidirectional"))
      (node (ref "U$12") (pin "5") (pinfunction "A4_5") (pintype "bidirectional"))
    )
    (net (code "31") (name "LCD_R{slash}W") (class "Default")
      (node (ref "U$1") (pin "P96") (pinfunction "RG7_P96") (pintype "bidirectional"))
      (node (ref "U$12") (pin "4") (pinfunction "A3_4") (pintype "bidirectional"))
    )
    (net (code "32") (name "MCLR") (class "Default")
      (node (ref "R16") (pin "2") (pinfunction "2_2") (pintype "passive"))
      (node (ref "SV1") (pin "6") (pinfunction "6_6") (pintype "passive"))
      (node (ref "U$1") (pin "P11") (pinfunction "MCLR_P11") (pintype "bidirectional"))
    )
    (net (code "33") (name "MIC_SIG") (class "Default")
      (node (ref "R7") (pin "1") (pinfunction "1_1") (pintype "passive"))
      (node (ref "U$1") (pin "P25") (pinfunction "RH6_P25") (pintype "bidirectional"))
    )
    (net (code "34") (name "MOTOR_LA") (class "Default")
      (node (ref "U$1") (pin "P70") (pinfunction "RB2_P70") (pintype "bidirectional"))
      (node (ref "U$8") (pin "OUTA") (pinfunction "OUTA_OUTA") (pintype "bidirectional"))
    )
    (net (code "35") (name "MOTOR_LB") (class "Default")
      (node (ref "U$1") (pin "P69") (pinfunction "RB3_P69") (pintype "bidirectional"))
      (node (ref "U$8") (pin "OUTB") (pinfunction "OUTB_OUTB") (pintype "bidirectional"))
    )
    (net (code "36") (name "MOTOR_RA") (class "Default")
      (node (ref "U$1") (pin "P72") (pinfunction "RB1_P72") (pintype "bidirectional"))
      (node (ref "U$9") (pin "OUTA") (pinfunction "OUTA_OUTA") (pintype "bidirectional"))
    )
    (net (code "37") (name "MOTOR_RB") (class "Default")
      (node (ref "U$1") (pin "P73") (pinfunction "RB0_P73") (pintype "bidirectional"))
      (node (ref "U$9") (pin "OUTB") (pinfunction "OUTB_OUTB") (pintype "bidirectional"))
    )
    (net (code "38") (name "Net-(3V3_REG-VIN)") (class "Default")
      (node (ref "3V3_REG") (pin "3") (pinfunction "VIN_3") (pintype "input"))
      (node (ref "C2") (pin "+") (pinfunction "+_+") (pintype "passive"))
      (node (ref "D1") (pin "C") (pinfunction "C_C") (pintype "passive"))
    )
    (net (code "39") (name "Net-(5V_REG-VIN)") (class "Default")
      (node (ref "5V_REG") (pin "3") (pinfunction "VIN_3") (pintype "bidirectional"))
      (node (ref "C1") (pin "+") (pinfunction "+_+") (pintype "passive"))
      (node (ref "D2") (pin "C") (pinfunction "C_C") (pintype "passive"))
    )
    (net (code "40") (name "Net-(C12-Pad1)") (class "Default")
      (node (ref "C12") (pin "1") (pinfunction "1_1") (pintype "passive"))
      (node (ref "M1") (pin "2") (pinfunction "2_2") (pintype "passive"))
      (node (ref "R4") (pin "1") (pinfunction "1_1") (pintype "passive"))
    )
    (net (code "41") (name "Net-(C12-Pad2)") (class "Default")
      (node (ref "C12") (pin "2") (pinfunction "2_2") (pintype "passive"))
      (node (ref "R1") (pin "1") (pinfunction "1_1") (pintype "passive"))
    )
    (net (code "42") (name "Net-(C22-Pad2)") (class "Default")
      (node (ref "C22") (pin "2") (pinfunction "2_2") (pintype "passive"))
      (node (ref "U$10") (pin "CCP") (pinfunction "CCP_CCP") (pintype "bidirectional"))
    )
    (net (code "43") (name "Net-(C25-Pad2)") (class "Default")
      (node (ref "C25") (pin "2") (pinfunction "2_2") (pintype "passive"))
      (node (ref "U$11") (pin "CCP") (pinfunction "CCP_CCP") (pintype "bidirectional"))
    )
    (net (code "44") (name "Net-(C30-Pad1)") (class "Default")
      (node (ref "C30") (pin "1") (pinfunction "1_1") (pintype "passive"))
      (node (ref "R16") (pin "1") (pinfunction "1_1") (pintype "passive"))
      (node (ref "R17") (pin "1") (pinfunction "1_1") (pintype "passive"))
    )
    (net (code "45") (name "Net-(IC1-3V3OUT)") (class "Default")
      (node (ref "C5") (pin "1") (pinfunction "1_1") (pintype "passive"))
      (node (ref "IC1") (pin "17") (pinfunction "3V3OUT_17") (pintype "output"))
    )
    (net (code "46") (name "Net-(IC1-RXD)") (class "Default")
      (node (ref "IC1") (pin "5") (pinfunction "RXD_5") (pintype "input"))
      (node (ref "R11") (pin "1") (pinfunction "1_1") (pintype "passive"))
    )
    (net (code "47") (name "Net-(IC1-TXD)") (class "Default")
      (node (ref "IC1") (pin "1") (pinfunction "TXD_1") (pintype "output"))
      (node (ref "R10") (pin "1") (pinfunction "1_1") (pintype "passive"))
    )
    (net (code "48") (name "Net-(IC1-USBDM)") (class "Default")
      (node (ref "IC1") (pin "16") (pinfunction "USBDM_16") (pintype "bidirectional"))
      (node (ref "U$2") (pin "D-") (pinfunction "D-_D-") (pintype "bidirectional"))
    )
    (net (code "49") (name "Net-(IC1-USBDP)") (class "Default")
      (node (ref "IC1") (pin "15") (pinfunction "USBDP_15") (pintype "bidirectional"))
      (node (ref "U$2") (pin "D+") (pinfunction "D+_D+") (pintype "bidirectional"))
    )
    (net (code "50") (name "Net-(IC1-VCC)") (class "Default")
      (node (ref "C6") (pin "+") (pinfunction "+_+") (pintype "passive"))
      (node (ref "C7") (pin "1") (pinfunction "1_1") (pintype "passive"))
      (node (ref "IC1") (pin "20") (pinfunction "VCC_20") (pintype "power_in"))
      (node (ref "U$2") (pin "VCC") (pinfunction "VCC_VCC") (pintype "bidirectional"))
    )
    (net (code "51") (name "Net-(IC1-~{CTS})") (class "Default")
      (node (ref "IC1") (pin "11") (pinfunction "~{CTS}_11") (pintype "input"))
      (node (ref "R12") (pin "1") (pinfunction "1_1") (pintype "passive"))
    )
    (net (code "52") (name "Net-(IC1-~{DTR})") (class "Default")
      (node (ref "IC1") (pin "2") (pinfunction "~{DTR}_2") (pintype "output"))
      (node (ref "R13") (pin "1") (pinfunction "1_1") (pintype "passive"))
    )
    (net (code "53") (name "Net-(U$1A-VCAP)") (class "Default")
      (node (ref "C29") (pin "1") (pinfunction "1_1") (pintype "passive"))
      (node (ref "U$1") (pin "P15") (pinfunction "VCAP_P15") (pintype "bidirectional"))
    )
    (net (code "54") (name "Net-(U$3-C1)") (class "Default")
      (node (ref "C9") (pin "1") (pinfunction "1_1") (pintype "passive"))
      (node (ref "U$3") (pin "P$10") (pinfunction "C1_P$10") (pintype "bidirectional"))
    )
    (net (code "55") (name "Net-(U$3-SCL)") (class "Default")
      (node (ref "R8") (pin "1") (pinfunction "1_1") (pintype "passive"))
      (node (ref "U$3") (pin "P$1") (pinfunction "SCL_P$1") (pintype "bidirectional"))
    )
    (net (code "56") (name "Net-(U$3-SDA)") (class "Default")
      (node (ref "R9") (pin "1") (pinfunction "1_1") (pintype "passive"))
      (node (ref "U$3") (pin "P$16") (pinfunction "SDA_P$16") (pintype "bidirectional"))
    )
    (net (code "57") (name "Net-(U$3-SETC)") (class "Default")
      (node (ref "C8") (pin "2") (pinfunction "2_2") (pintype "passive"))
      (node (ref "U$3") (pin "P$12") (pinfunction "SETC_P$12") (pintype "bidirectional"))
    )
    (net (code "58") (name "Net-(U$3-SETP)") (class "Default")
      (node (ref "C8") (pin "1") (pinfunction "1_1") (pintype "passive"))
      (node (ref "U$3") (pin "P$8") (pinfunction "SETP_P$8") (pintype "bidirectional"))
    )
    (net (code "59") (name "Net-(U$4-IN+)") (class "Default")
      (node (ref "C13") (pin "1") (pinfunction "1_1") (pintype "passive"))
      (node (ref "R1") (pin "2") (pinfunction "2_2") (pintype "passive"))
      (node (ref "R2") (pin "1") (pinfunction "1_1") (pintype "passive"))
      (node (ref "U$4") (pin "P$3") (pinfunction "IN+_P$3") (pintype "bidirectional"))
    )
    (net (code "60") (name "Net-(U$4-IN-)") (class "Default")
      (node (ref "C11") (pin "1") (pinfunction "1_1") (pintype "passive"))
      (node (ref "R5") (pin "1") (pinfunction "1_1") (pintype "passive"))
      (node (ref "R6") (pin "2") (pinfunction "2_2") (pintype "passive"))
      (node (ref "U$4") (pin "P$4") (pinfunction "IN-_P$4") (pintype "bidirectional"))
    )
    (net (code "61") (name "Net-(U$4-VOUT)") (class "Default")
      (node (ref "C13") (pin "2") (pinfunction "2_2") (pintype "passive"))
      (node (ref "R2") (pin "2") (pinfunction "2_2") (pintype "passive"))
      (node (ref "R7") (pin "2") (pinfunction "2_2") (pintype "passive"))
      (node (ref "U$4") (pin "P$1") (pinfunction "VOUT_P$1") (pintype "bidirectional"))
    )
    (net (code "62") (name "Net-(U$6-2)") (class "Default")
      (node (ref "LCD") (pin "3") (pinfunction "3_3") (pintype "passive"))
      (node (ref "U$6") (pin "P$2") (pinfunction "2_P$2") (pintype "bidirectional"))
    )
    (net (code "63") (name "Net-(U$10-OUT1-PadOUT1_1)") (class "Default")
      (node (ref "U$10") (pin "OUT1_1") (pinfunction "OUT1_OUT1_1") (pintype "bidirectional"))
      (node (ref "U$10") (pin "OUT1_2") (pinfunction "OUT1_OUT1_2") (pintype "bidirectional"))
      (node (ref "U$10") (pin "OUT1_3") (pinfunction "OUT1_OUT1_3") (pintype "bidirectional"))
      (node (ref "U$10") (pin "OUT1_4") (pinfunction "OUT1_OUT1_4") (pintype "bidirectional"))
      (node (ref "U$8") (pin "M1") (pinfunction "M1_M1") (pintype "bidirectional"))
    )
    (net (code "64") (name "Net-(U$10-OUT2-PadOUT2_1)") (class "Default")
      (node (ref "U$10") (pin "OUT2_1") (pinfunction "OUT2_OUT2_1") (pintype "bidirectional"))
      (node (ref "U$10") (pin "OUT2_2") (pinfunction "OUT2_OUT2_2") (pintype "bidirectional"))
      (node (ref "U$10") (pin "OUT2_3") (pinfunction "OUT2_OUT2_3") (pintype "bidirectional"))
      (node (ref "U$10") (pin "OUT2_4") (pinfunction "OUT2_OUT2_4") (pintype "bidirectional"))
      (node (ref "U$8") (pin "M2") (pinfunction "M2_M2") (pintype "bidirectional"))
    )
    (net (code "65") (name "Net-(U$11-OUT1-PadOUT1_1)") (class "Default")
      (node (ref "U$11") (pin "OUT1_1") (pinfunction "OUT1_OUT1_1") (pintype "bidirectional"))
      (node (ref "U$11") (pin "OUT1_2") (pinfunction "OUT1_OUT1_2") (pintype "bidirectional"))
      (node (ref "U$11") (pin "OUT1_3") (pinfunction "OUT1_OUT1_3") (pintype "bidirectional"))
      (node (ref "U$11") (pin "OUT1_4") (pinfunction "OUT1_OUT1_4") (pintype "bidirectional"))
      (node (ref "U$9") (pin "M1") (pinfunction "M1_M1") (pintype "bidirectional"))
    )
    (net (code "66") (name "Net-(U$11-OUT2-PadOUT2_1)") (class "Default")
      (node (ref "U$11") (pin "OUT2_1") (pinfunction "OUT2_OUT2_1") (pintype "bidirectional"))
      (node (ref "U$11") (pin "OUT2_2") (pinfunction "OUT2_OUT2_2") (pintype "bidirectional"))
      (node (ref "U$11") (pin "OUT2_3") (pinfunction "OUT2_OUT2_3") (pintype "bidirectional"))
      (node (ref "U$11") (pin "OUT2_4") (pinfunction "OUT2_OUT2_4") (pintype "bidirectional"))
      (node (ref "U$9") (pin "M2") (pinfunction "M2_M2") (pintype "bidirectional"))
    )
    (net (code "67") (name "Net-(U$12-B1)") (class "Default")
      (node (ref "LCD") (pin "7") (pinfunction "7_7") (pintype "passive"))
      (node (ref "U$12") (pin "13") (pinfunction "B1_13") (pintype "bidirectional"))
    )
    (net (code "68") (name "Net-(U$12-B2)") (class "Default")
      (node (ref "LCD") (pin "6") (pinfunction "6_6") (pintype "passive"))
      (node (ref "U$12") (pin "12") (pinfunction "B2_12") (pintype "bidirectional"))
    )
    (net (code "69") (name "Net-(U$12-B3)") (class "Default")
      (node (ref "LCD") (pin "5") (pinfunction "5_5") (pintype "passive"))
      (node (ref "U$12") (pin "11") (pinfunction "B3_11") (pintype "bidirectional"))
    )
    (net (code "70") (name "Net-(U$12-B4)") (class "Default")
      (node (ref "LCD") (pin "4") (pinfunction "4_4") (pintype "passive"))
      (node (ref "U$12") (pin "10") (pinfunction "B4_10") (pintype "bidirectional"))
    )
    (net (code "71") (name "Net-(U$13-B1)") (class "Default")
      (node (ref "LCD") (pin "11") (pinfunction "11_11") (pintype "passive"))
      (node (ref "U$13") (pin "13") (pinfunction "B1_13") (pintype "bidirectional"))
    )
    (net (code "72") (name "Net-(U$13-B2)") (class "Default")
      (node (ref "LCD") (pin "10") (pinfunction "10_10") (pintype "passive"))
      (node (ref "U$13") (pin "12") (pinfunction "B2_12") (pintype "bidirectional"))
    )
    (net (code "73") (name "Net-(U$13-B3)") (class "Default")
      (node (ref "LCD") (pin "9") (pinfunction "9_9") (pintype "passive"))
      (node (ref "U$13") (pin "11") (pinfunction "B3_11") (pintype "bidirectional"))
    )
    (net (code "74") (name "Net-(U$13-B4)") (class "Default")
      (node (ref "LCD") (pin "8") (pinfunction "8_8") (pintype "passive"))
      (node (ref "U$13") (pin "10") (pinfunction "B4_10") (pintype "bidirectional"))
    )
    (net (code "75") (name "Net-(U$14-B2)") (class "Default")
      (node (ref "LCD") (pin "14") (pinfunction "14_14") (pintype "passive"))
      (node (ref "U$14") (pin "12") (pinfunction "B2_12") (pintype "bidirectional"))
    )
    (net (code "76") (name "Net-(U$14-B3)") (class "Default")
      (node (ref "LCD") (pin "13") (pinfunction "13_13") (pintype "passive"))
      (node (ref "U$14") (pin "11") (pinfunction "B3_11") (pintype "bidirectional"))
    )
    (net (code "77") (name "Net-(U$14-B4)") (class "Default")
      (node (ref "LCD") (pin "12") (pinfunction "12_12") (pintype "passive"))
      (node (ref "U$14") (pin "10") (pinfunction "B4_10") (pintype "bidirectional"))
    )
    (net (code "78") (name "Net-(U1-SCL)") (class "Default")
      (node (ref "R15") (pin "1") (pinfunction "1_1") (pintype "passive"))
      (node (ref "U1") (pin "P$2") (pinfunction "SCL_P$2") (pintype "bidirectional"))
    )
    (net (code "79") (name "Net-(U1-SDA)") (class "Default")
      (node (ref "R14") (pin "1") (pinfunction "1_1") (pintype "passive"))
      (node (ref "U1") (pin "P$6") (pinfunction "SDA_P$6") (pintype "bidirectional"))
    )
    (net (code "80") (name "PGC") (class "Default")
      (node (ref "SV1") (pin "2") (pinfunction "2_2") (pintype "passive"))
      (node (ref "U$1") (pin "P65") (pinfunction "RB6_P65") (pintype "bidirectional"))
    )
    (net (code "81") (name "PGD") (class "Default")
      (node (ref "SV1") (pin "3") (pinfunction "3_3") (pintype "passive"))
      (node (ref "U$1") (pin "P58") (pinfunction "RB7_P58") (pintype "bidirectional"))
    )
    (net (code "82") (name "PIXY_RX") (class "Default")
      (node (ref "U$1") (pin "P53") (pinfunction "RC2_P53") (pintype "bidirectional"))
      (node (ref "U$15") (pin "1") (pinfunction "1_1") (pintype "bidirectional"))
    )
    (net (code "83") (name "PIXY_TX") (class "Default")
      (node (ref "U$1") (pin "P57") (pinfunction "RC5_P57") (pintype "bidirectional"))
      (node (ref "U$15") (pin "4") (pinfunction "4_4") (pintype "bidirectional"))
    )
    (net (code "84") (name "RST1") (class "Default")
      (node (ref "IR_CAM") (pin "2") (pinfunction "2_2") (pintype "passive"))
      (node (ref "U$1") (pin "P47") (pinfunction "RC6_P47") (pintype "bidirectional"))
    )
    (net (code "85") (name "RST2") (class "Default")
      (node (ref "IR_CAM") (pin "1") (pinfunction "1_1") (pintype "passive"))
      (node (ref "U$1") (pin "P48") (pinfunction "RC7_P48") (pintype "bidirectional"))
    )
    (net (code "86") (name "SERVO_SIGNAL") (class "Default")
      (node (ref "SERVO") (pin "3") (pinfunction "3_3") (pintype "passive"))
      (node (ref "U$1") (pin "P26") (pinfunction "RH5_P26") (pintype "bidirectional"))
    )
    (net (code "87") (name "SW1") (class "Default")
      (node (ref "SW1") (pin "1") (pinfunction "1_1") (pintype "passive"))
      (node (ref "U$1") (pin "P13") (pinfunction "RL2_P13") (pintype "bidirectional"))
    )
    (net (code "88") (name "SW2") (class "Default")
      (node (ref "SW1") (pin "2") (pinfunction "2_2") (pintype "passive"))
      (node (ref "U$1") (pin "P12") (pinfunction "RG4_P12") (pintype "bidirectional"))
    )
    (net (code "89") (name "SW3") (class "Default")
      (node (ref "SW1") (pin "3") (pinfunction "3_3") (pintype "passive"))
      (node (ref "U$1") (pin "P10") (pinfunction "RL1_P10") (pintype "bidirectional"))
    )
    (net (code "90") (name "SW4") (class "Default")
      (node (ref "SW1") (pin "4") (pinfunction "4_4") (pintype "passive"))
      (node (ref "U$1") (pin "P9") (pinfunction "RG3_P9") (pintype "bidirectional"))
    )
    (net (code "91") (name "SW5") (class "Default")
      (node (ref "SW1") (pin "5") (pinfunction "5_5") (pintype "passive"))
      (node (ref "U$1") (pin "P8") (pinfunction "RG2_P8") (pintype "bidirectional"))
    )
    (net (code "92") (name "SW6") (class "Default")
      (node (ref "SW1") (pin "6") (pinfunction "6_6") (pintype "passive"))
      (node (ref "U$1") (pin "P7") (pinfunction "RG1_P7") (pintype "bidirectional"))
    )
    (net (code "93") (name "SW7") (class "Default")
      (node (ref "SW1") (pin "7") (pinfunction "7_7") (pintype "passive"))
      (node (ref "U$1") (pin "P6") (pinfunction "RG0_P6") (pintype "bidirectional"))
    )
    (net (code "94") (name "USB_CTS") (class "Default")
      (node (ref "R12") (pin "2") (pinfunction "2_2") (pintype "passive"))
      (node (ref "U$1") (pin "P86") (pinfunction "RD1_P86") (pintype "bidirectional"))
    )
    (net (code "95") (name "USB_DTR") (class "Default")
      (node (ref "R13") (pin "2") (pinfunction "2_2") (pintype "passive"))
      (node (ref "U$1") (pin "P83") (pinfunction "RD3_P83") (pintype "bidirectional"))
    )
    (net (code "96") (name "USB_RXD") (class "Default")
      (node (ref "R11") (pin "2") (pinfunction "2_2") (pintype "passive"))
      (node (ref "U$1") (pin "P84") (pinfunction "RD2_P84") (pintype "bidirectional"))
    )
    (net (code "97") (name "USB_TXD") (class "Default")
      (node (ref "R10") (pin "2") (pinfunction "2_2") (pintype "passive"))
      (node (ref "U$1") (pin "P82") (pinfunction "RD4_P82") (pintype "bidirectional"))
    )
    (net (code "98") (name "V+") (class "Default")
      (node (ref "BATT_CON") (pin "1") (pinfunction "2_1") (pintype "passive"))
      (node (ref "C22") (pin "1") (pinfunction "1_1") (pintype "passive"))
      (node (ref "C23") (pin "1") (pinfunction "1_1") (pintype "passive"))
      (node (ref "C24") (pin "+") (pinfunction "+_+") (pintype "passive"))
      (node (ref "C25") (pin "1") (pinfunction "1_1") (pintype "passive"))
      (node (ref "C26") (pin "1") (pinfunction "1_1") (pintype "passive"))
      (node (ref "C27") (pin "+") (pinfunction "+_+") (pintype "passive"))
      (node (ref "D1") (pin "A") (pinfunction "A_A") (pintype "passive"))
      (node (ref "D2") (pin "A") (pinfunction "A_A") (pintype "passive"))
      (node (ref "U$10") (pin "VPWR") (pinfunction "VPWR_VPWR") (pintype "bidirectional"))
      (node (ref "U$10") (pin "VPWR1") (pinfunction "VPWR_VPWR1") (pintype "bidirectional"))
      (node (ref "U$10") (pin "VPWR2") (pinfunction "VPWR_VPWR2") (pintype "bidirectional"))
      (node (ref "U$10") (pin "VPWR_2") (pinfunction "VPWR_VPWR_2") (pintype "bidirectional"))
      (node (ref "U$11") (pin "VPWR") (pinfunction "VPWR_VPWR") (pintype "bidirectional"))
      (node (ref "U$11") (pin "VPWR1") (pinfunction "VPWR_VPWR1") (pintype "bidirectional"))
      (node (ref "U$11") (pin "VPWR2") (pinfunction "VPWR_VPWR2") (pintype "bidirectional"))
      (node (ref "U$11") (pin "VPWR_2") (pinfunction "VPWR_VPWR_2") (pintype "bidirectional"))
    )
    (net (code "99") (name "VCCIO") (class "Default")
      (node (ref "IC1") (pin "4") (pinfunction "VCCIO_4") (pintype "power_in"))
    )
    (net (code "100") (name "unconnected-(IC1-CBUS0-Pad23)") (class "Default")
      (node (ref "IC1") (pin "23") (pinfunction "CBUS0_23") (pintype "bidirectional"))
    )
    (net (code "101") (name "unconnected-(IC1-CBUS1-Pad22)") (class "Default")
      (node (ref "IC1") (pin "22") (pinfunction "CBUS1_22") (pintype "bidirectional"))
    )
    (net (code "102") (name "unconnected-(IC1-CBUS2-Pad13)") (class "Default")
      (node (ref "IC1") (pin "13") (pinfunction "CBUS2_13") (pintype "bidirectional"))
    )
    (net (code "103") (name "unconnected-(IC1-CBUS3-Pad14)") (class "Default")
      (node (ref "IC1") (pin "14") (pinfunction "CBUS3_14") (pintype "bidirectional"))
    )
    (net (code "104") (name "unconnected-(IC1-CBUS4-Pad12)") (class "Default")
      (node (ref "IC1") (pin "12") (pinfunction "CBUS4_12") (pintype "bidirectional"))
    )
    (net (code "105") (name "unconnected-(IC1-OSCI-Pad27)") (class "Default")
      (node (ref "IC1") (pin "27") (pinfunction "OSCI_27") (pintype "input"))
    )
    (net (code "106") (name "unconnected-(IC1-OSCO-Pad28)") (class "Default")
      (node (ref "IC1") (pin "28") (pinfunction "OSCO_28") (pintype "output"))
    )
    (net (code "107") (name "unconnected-(IC1-~{DCD}-Pad10)") (class "Default")
      (node (ref "IC1") (pin "10") (pinfunction "~{DCD}_10") (pintype "input"))
    )
    (net (code "108") (name "unconnected-(IC1-~{DSR}-Pad9)") (class "Default")
      (node (ref "IC1") (pin "9") (pinfunction "~{DSR}_9") (pintype "input"))
    )
    (net (code "109") (name "unconnected-(IC1-~{RESET}-Pad19)") (class "Default")
      (node (ref "IC1") (pin "19") (pinfunction "~{RESET}_19") (pintype "input"))
    )
    (net (code "110") (name "unconnected-(IC1-~{RI}-Pad6)") (class "Default")
      (node (ref "IC1") (pin "6") (pinfunction "~{RI}_6") (pintype "input"))
    )
    (net (code "111") (name "unconnected-(IC1-~{RTS}-Pad3)") (class "Default")
      (node (ref "IC1") (pin "3") (pinfunction "~{RTS}_3") (pintype "output"))
    )
    (net (code "112") (name "unconnected-(SV1-Pad1)") (class "Default")
      (node (ref "SV1") (pin "1") (pinfunction "1_1") (pintype "passive"))
    )
    (net (code "113") (name "unconnected-(U$1A-VBAT-PadP29)") (class "Default")
      (node (ref "U$1") (pin "P29") (pinfunction "VBAT_P29") (pintype "bidirectional"))
    )
    (net (code "114") (name "unconnected-(U$1A-VUSB-PadP28)") (class "Default")
      (node (ref "U$1") (pin "P28") (pinfunction "VUSB_P28") (pintype "bidirectional"))
    )
    (net (code "115") (name "unconnected-(U$1B-RJ0-PadP77)") (class "Default")
      (node (ref "U$1") (pin "P77") (pinfunction "RJ0_P77") (pintype "bidirectional"))
    )
    (net (code "116") (name "unconnected-(U$1B-RJ1-PadP76)") (class "Default")
      (node (ref "U$1") (pin "P76") (pinfunction "RJ1_P76") (pintype "bidirectional"))
    )
    (net (code "117") (name "unconnected-(U$1B-RJ2-PadP75)") (class "Default")
      (node (ref "U$1") (pin "P75") (pinfunction "RJ2_P75") (pintype "bidirectional"))
    )
    (net (code "118") (name "unconnected-(U$1B-RJ3-PadP74)") (class "Default")
      (node (ref "U$1") (pin "P74") (pinfunction "RJ3_P74") (pintype "bidirectional"))
    )
    (net (code "119") (name "unconnected-(U$1B-RJ4-PadP49)") (class "Default")
      (node (ref "U$1") (pin "P49") (pinfunction "RJ4_P49") (pintype "bidirectional"))
    )
    (net (code "120") (name "unconnected-(U$1B-RJ5-PadP50)") (class "Default")
      (node (ref "U$1") (pin "P50") (pinfunction "RJ5_P50") (pintype "bidirectional"))
    )
    (net (code "121") (name "unconnected-(U$1B-RJ6-PadP51)") (class "Default")
      (node (ref "U$1") (pin "P51") (pinfunction "RJ6_P51") (pintype "bidirectional"))
    )
    (net (code "122") (name "unconnected-(U$1B-RJ7-PadP52)") (class "Default")
      (node (ref "U$1") (pin "P52") (pinfunction "RJ7_P52") (pintype "bidirectional"))
    )
    (net (code "123") (name "unconnected-(U$1C-RK0-PadP46)") (class "Default")
      (node (ref "U$1") (pin "P46") (pinfunction "RK0_P46") (pintype "bidirectional"))
    )
    (net (code "124") (name "unconnected-(U$1C-RK1-PadP55)") (class "Default")
      (node (ref "U$1") (pin "P55") (pinfunction "RK1_P55") (pintype "bidirectional"))
    )
    (net (code "125") (name "unconnected-(U$1C-RK2-PadP60)") (class "Default")
      (node (ref "U$1") (pin "P60") (pinfunction "RK2_P60") (pintype "bidirectional"))
    )
    (net (code "126") (name "unconnected-(U$1C-RK3-PadP63)") (class "Default")
      (node (ref "U$1") (pin "P63") (pinfunction "RK3_P63") (pintype "bidirectional"))
    )
    (net (code "127") (name "unconnected-(U$1C-RK4-PadP66)") (class "Default")
      (node (ref "U$1") (pin "P66") (pinfunction "RK4_P66") (pintype "bidirectional"))
    )
    (net (code "128") (name "unconnected-(U$1C-RK5-PadP71)") (class "Default")
      (node (ref "U$1") (pin "P71") (pinfunction "RK5_P71") (pintype "bidirectional"))
    )
    (net (code "129") (name "unconnected-(U$1C-RK6-PadP80)") (class "Default")
      (node (ref "U$1") (pin "P80") (pinfunction "RK6_P80") (pintype "bidirectional"))
    )
    (net (code "130") (name "unconnected-(U$1C-RK7-PadP85)") (class "Default")
      (node (ref "U$1") (pin "P85") (pinfunction "RK7_P85") (pintype "bidirectional"))
    )
    (net (code "131") (name "unconnected-(U$1D-RL4-PadP21)") (class "Default")
      (node (ref "U$1") (pin "P21") (pinfunction "RL4_P21") (pintype "bidirectional"))
    )
    (net (code "132") (name "unconnected-(U$1D-RL5-PadP30)") (class "Default")
      (node (ref "U$1") (pin "P30") (pinfunction "RL5_P30") (pintype "bidirectional"))
    )
    (net (code "133") (name "unconnected-(U$1D-RL6-PadP38)") (class "Default")
      (node (ref "U$1") (pin "P38") (pinfunction "RL6_P38") (pintype "bidirectional"))
    )
    (net (code "134") (name "unconnected-(U$1D-RL7-PadP41)") (class "Default")
      (node (ref "U$1") (pin "P41") (pinfunction "RL7_P41") (pintype "bidirectional"))
    )
    (net (code "135") (name "unconnected-(U$1E-RA0-PadP337)") (class "Default")
      (node (ref "U$1") (pin "P337") (pinfunction "RA0_P337") (pintype "bidirectional"))
    )
    (net (code "136") (name "unconnected-(U$1E-RA1-PadP36)") (class "Default")
      (node (ref "U$1") (pin "P36") (pinfunction "RA1_P36") (pintype "bidirectional"))
    )
    (net (code "137") (name "unconnected-(U$1E-RA2-PadP34)") (class "Default")
      (node (ref "U$1") (pin "P34") (pinfunction "RA2_P34") (pintype "bidirectional"))
    )
    (net (code "138") (name "unconnected-(U$1E-RA3-PadP33)") (class "Default")
      (node (ref "U$1") (pin "P33") (pinfunction "RA3_P33") (pintype "bidirectional"))
    )
    (net (code "139") (name "unconnected-(U$1E-RA4-PadP43)") (class "Default")
      (node (ref "U$1") (pin "P43") (pinfunction "RA4_P43") (pintype "bidirectional"))
    )
    (net (code "140") (name "unconnected-(U$1E-RA5-PadP42)") (class "Default")
      (node (ref "U$1") (pin "P42") (pinfunction "RA5_P42") (pintype "bidirectional"))
    )
    (net (code "141") (name "unconnected-(U$1E-RA6-PadP62)") (class "Default")
      (node (ref "U$1") (pin "P62") (pinfunction "RA6_P62") (pintype "bidirectional"))
    )
    (net (code "142") (name "unconnected-(U$1E-RA7-PadP61)") (class "Default")
      (node (ref "U$1") (pin "P61") (pinfunction "RA7_P61") (pintype "bidirectional"))
    )
    (net (code "143") (name "unconnected-(U$1G-RC0-PadP45)") (class "Default")
      (node (ref "U$1") (pin "P45") (pinfunction "RC0_P45") (pintype "bidirectional"))
    )
    (net (code "144") (name "unconnected-(U$1G-RC1-PadP44)") (class "Default")
      (node (ref "U$1") (pin "P44") (pinfunction "RC1_P44") (pintype "bidirectional"))
    )
    (net (code "145") (name "unconnected-(U$1J-RF7-PadP17)") (class "Default")
      (node (ref "U$1") (pin "P17") (pinfunction "RF7_P17") (pintype "bidirectional"))
    )
    (net (code "146") (name "unconnected-(U$1K-RG6-PadP89)") (class "Default")
      (node (ref "U$1") (pin "P89") (pinfunction "RG6_P89") (pintype "bidirectional"))
    )
    (net (code "147") (name "unconnected-(U$1L-RH4-PadP27)") (class "Default")
      (node (ref "U$1") (pin "P27") (pinfunction "RH4_P27") (pintype "bidirectional"))
    )
    (net (code "148") (name "unconnected-(U$1L-RH7-PadP24)") (class "Default")
      (node (ref "U$1") (pin "P24") (pinfunction "RH7_P24") (pintype "bidirectional"))
    )
    (net (code "149") (name "unconnected-(U$2-PadID)") (class "Default")
      (node (ref "U$2") (pin "ID") (pinfunction "ID_ID") (pintype "bidirectional"))
    )
    (net (code "150") (name "unconnected-(U$3-DRDY-PadP$15)") (class "Default")
      (node (ref "U$3") (pin "P$15") (pinfunction "DRDY_P$15") (pintype "bidirectional"))
    )
    (net (code "151") (name "unconnected-(U$10-PadD1)") (class "Default")
      (node (ref "U$10") (pin "D1") (pinfunction "D1_D1") (pintype "bidirectional"))
    )
    (net (code "152") (name "unconnected-(U$10-PadD2)") (class "Default")
      (node (ref "U$10") (pin "D2") (pinfunction "D2_D2") (pintype "bidirectional"))
    )
    (net (code "153") (name "unconnected-(U$10-PadEN)") (class "Default")
      (node (ref "U$10") (pin "EN") (pinfunction "EN_EN") (pintype "bidirectional"))
    )
    (net (code "154") (name "unconnected-(U$10-PadFB)") (class "Default")
      (node (ref "U$10") (pin "FB") (pinfunction "FB_FB") (pintype "bidirectional"))
    )
    (net (code "155") (name "unconnected-(U$10-PadIN1)") (class "Default")
      (node (ref "U$10") (pin "IN1") (pinfunction "IN1_IN1") (pintype "bidirectional"))
    )
    (net (code "156") (name "unconnected-(U$10-PadIN2)") (class "Default")
      (node (ref "U$10") (pin "IN2") (pinfunction "IN2_IN2") (pintype "bidirectional"))
    )
    (net (code "157") (name "unconnected-(U$10-PadINV)") (class "Default")
      (node (ref "U$10") (pin "INV") (pinfunction "INV_INV") (pintype "bidirectional"))
    )
    (net (code "158") (name "unconnected-(U$10-PadSF)") (class "Default")
      (node (ref "U$10") (pin "SF") (pinfunction "SF_SF") (pintype "bidirectional"))
    )
    (net (code "159") (name "unconnected-(U$10-PadSLEW)") (class "Default")
      (node (ref "U$10") (pin "SLEW") (pinfunction "SLEW_SLEW") (pintype "bidirectional"))
    )
    (net (code "160") (name "unconnected-(U$11-PadD1)") (class "Default")
      (node (ref "U$11") (pin "D1") (pinfunction "D1_D1") (pintype "bidirectional"))
    )
    (net (code "161") (name "unconnected-(U$11-PadD2)") (class "Default")
      (node (ref "U$11") (pin "D2") (pinfunction "D2_D2") (pintype "bidirectional"))
    )
    (net (code "162") (name "unconnected-(U$11-PadEN)") (class "Default")
      (node (ref "U$11") (pin "EN") (pinfunction "EN_EN") (pintype "bidirectional"))
    )
    (net (code "163") (name "unconnected-(U$11-PadFB)") (class "Default")
      (node (ref "U$11") (pin "FB") (pinfunction "FB_FB") (pintype "bidirectional"))
    )
    (net (code "164") (name "unconnected-(U$11-PadIN1)") (class "Default")
      (node (ref "U$11") (pin "IN1") (pinfunction "IN1_IN1") (pintype "bidirectional"))
    )
    (net (code "165") (name "unconnected-(U$11-PadIN2)") (class "Default")
      (node (ref "U$11") (pin "IN2") (pinfunction "IN2_IN2") (pintype "bidirectional"))
    )
    (net (code "166") (name "unconnected-(U$11-PadINV)") (class "Default")
      (node (ref "U$11") (pin "INV") (pinfunction "INV_INV") (pintype "bidirectional"))
    )
    (net (code "167") (name "unconnected-(U$11-PadSF)") (class "Default")
      (node (ref "U$11") (pin "SF") (pinfunction "SF_SF") (pintype "bidirectional"))
    )
    (net (code "168") (name "unconnected-(U$11-PadSLEW)") (class "Default")
      (node (ref "U$11") (pin "SLEW") (pinfunction "SLEW_SLEW") (pintype "bidirectional"))
    )
    (net (code "169") (name "unconnected-(U$15-Pad3)") (class "Default")
      (node (ref "U$15") (pin "3") (pinfunction "3_3") (pintype "bidirectional"))
    )
    (net (code "170") (name "unconnected-(U$15-Pad5)") (class "Default")
      (node (ref "U$15") (pin "5") (pinfunction "5_5") (pintype "bidirectional"))
    )
    (net (code "171") (name "unconnected-(U1-INT-PadP$5)") (class "Default")
      (node (ref "U1") (pin "P$5") (pinfunction "INT_P$5") (pintype "output"))
    )
    (net (code "172") (name "unconnected-(U1-NC-PadP$4)") (class "Default")
      (node (ref "U1") (pin "P$4") (pinfunction "NC_P$4") (pintype "no_connect"))
    )
  )
)
